# AnalogEx_1RedLedFadeInFadeOutUSB.net
KiCad netlist of a schematic drawn in EAGLE
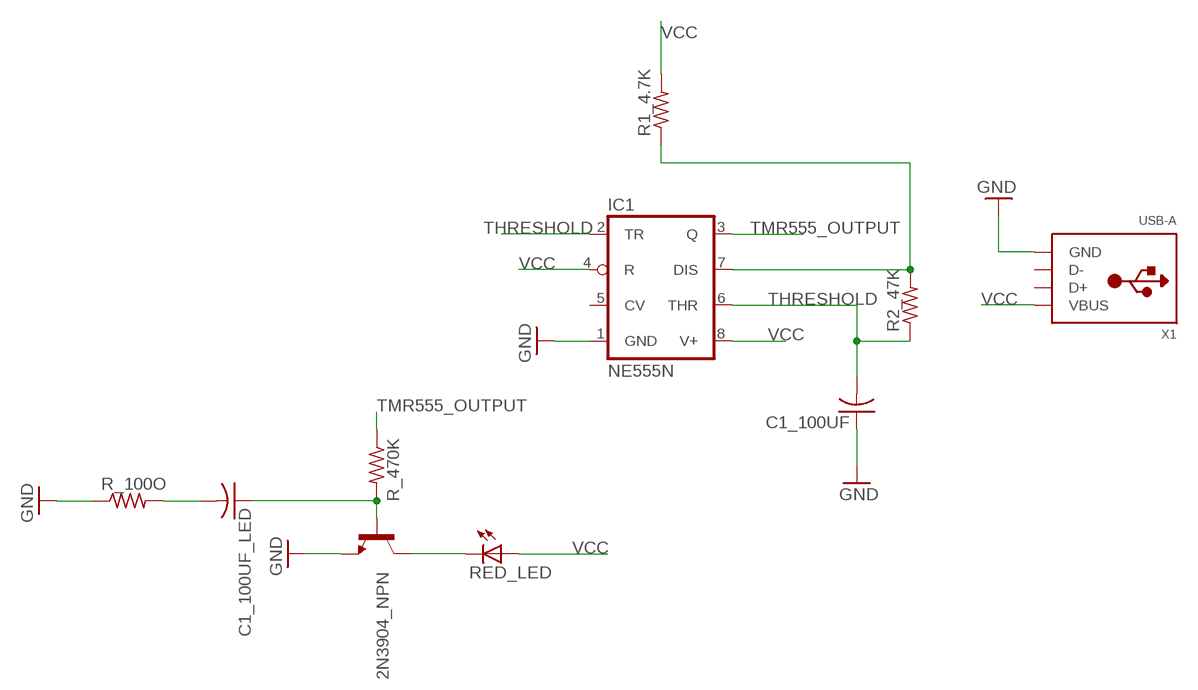
[diagram p0: schematic, sheet 1]

(export (version "E")
  (design (tool "Eeschema 10.0.6"))
  (components
    (comp (ref "2N3904_NPN")
      (value "MMBT3904LT1-NPN-SOT23-BEC")
      (footprint "eagle-import:SOT23-BEC")
      (libsource (lib "eagle-import") (part "-NPN-SOT23-BECMMBT3904LT1"))
    )
    (comp (ref "C1_100UF")
      (value "C-US025-030X050")
      (footprint "eagle-import:C025-030X050")
      (libsource (lib "eagle-import") (part "C-US025-030X050"))
    )
    (comp (ref "C1_100UF_LED")
      (value "C-US025-030X050")
      (footprint "eagle-import:C025-030X050")
      (libsource (lib "eagle-import") (part "C-US025-030X050"))
    )
    (comp (ref "IC1")
      (value "NE555N")
      (footprint "eagle-import:DIL08")
      (libsource (lib "eagle-import") (part "555NNE"))
    )
    (comp (ref "R1_4.7K")
      (value "R-US_R1206")
      (footprint "eagle-import:R1206")
      (libsource (lib "eagle-import") (part "R-US_R1206"))
    )
    (comp (ref "R2_47K")
      (value "R-US_R1206")
      (footprint "eagle-import:R1206")
      (libsource (lib "eagle-import") (part "R-US_R1206"))
    )
    (comp (ref "RED_LED")
      (value "LED5MM")
      (footprint "eagle-import:LED5MM")
      (libsource (lib "eagle-import") (part "LED5MM"))
    )
    (comp (ref "R_100O")
      (value "R-US_R1206")
      (footprint "eagle-import:R1206")
      (libsource (lib "eagle-import") (part "R-US_R1206"))
    )
    (comp (ref "R_470K")
      (value "R-US_R1206")
      (footprint "eagle-import:R1206")
      (libsource (lib "eagle-import") (part "R-US_R1206"))
    )
    (comp (ref "X1")
      (value "USB-A")
      (footprint "eagle-import:MOLEX_480371000")
      (libsource (lib "eagle-import") (part "USB-A"))
    )
  )
  (nets
    (net (code "1") (name "/THRESHOLD") (class "Default")
      (node (ref "C1_100UF") (pin "2") (pinfunction "2_2") (pintype "passive"))
      (node (ref "IC1") (pin "2") (pinfunction "TR_2") (pintype "input"))
      (node (ref "IC1") (pin "6") (pinfunction "THR_6") (pintype "input"))
      (node (ref "R2_47K") (pin "1") (pinfunction "1_1") (pintype "passive"))
    )
    (net (code "2") (name "/TMR555_OUTPUT") (class "Default")
      (node (ref "IC1") (pin "3") (pinfunction "Q_3") (pintype "output"))
      (node (ref "R_470K") (pin "1") (pinfunction "1_1") (pintype "passive"))
    )
    (net (code "3") (name "/VCC") (class "Default")
      (node (ref "IC1") (pin "4") (pinfunction "R_4") (pintype "input"))
      (node (ref "IC1") (pin "8") (pinfunction "V+_8") (pintype "power_in"))
      (node (ref "R1_4.7K") (pin "2") (pinfunction "2_2") (pintype "passive"))
      (node (ref "RED_LED") (pin "A") (pinfunction "A_A") (pintype "passive"))
      (node (ref "X1") (pin "1") (pinfunction "VBUS_1") (pintype "power_in"))
    )
    (net (code "4") (name "GND") (class "Default")
      (node (ref "2N3904_NPN") (pin "E") (pinfunction "E_E") (pintype "passive"))
      (node (ref "C1_100UF") (pin "1") (pinfunction "1_1") (pintype "passive"))
      (node (ref "IC1") (pin "1") (pinfunction "GND_1") (pintype "power_in"))
      (node (ref "R_100O") (pin "1") (pinfunction "1_1") (pintype "passive"))
      (node (ref "X1") (pin "4") (pinfunction "GND_4") (pintype "power_in"))
    )
    (net (code "5") (name "Net-(2N3904_NPN-PadB)") (class "Default")
      (node (ref "2N3904_NPN") (pin "B") (pinfunction "B_B") (pintype "passive"))
      (node (ref "C1_100UF_LED") (pin "1") (pinfunction "1_1") (pintype "passive"))
      (node (ref "R_470K") (pin "2") (pinfunction "2_2") (pintype "passive"))
    )
    (net (code "6") (name "Net-(C1_100UF_LED-Pad2)") (class "Default")
      (node (ref "C1_100UF_LED") (pin "2") (pinfunction "2_2") (pintype "passive"))
      (node (ref "R_100O") (pin "2") (pinfunction "2_2") (pintype "passive"))
    )
    (net (code "7") (name "Net-(IC1-DIS)") (class "Default")
      (node (ref "IC1") (pin "7") (pinfunction "DIS_7") (pintype "input"))
      (node (ref "R1_4.7K") (pin "1") (pinfunction "1_1") (pintype "passive"))
      (node (ref "R2_47K") (pin "2") (pinfunction "2_2") (pintype "passive"))
    )
    (net (code "8") (name "Net-(RED_LED-C)") (class "Default")
      (node (ref "2N3904_NPN") (pin "C") (pinfunction "C_C") (pintype "passive"))
      (node (ref "RED_LED") (pin "K") (pinfunction "C_K") (pintype "passive"))
    )
    (net (code "9") (name "unconnected-(IC1-CV-Pad5)") (class "Default")
      (node (ref "IC1") (pin "5") (pinfunction "CV_5") (pintype "input"))
    )
    (net (code "10") (name "unconnected-(X1-D+-Pad3)") (class "Default")
      (node (ref "X1") (pin "3") (pinfunction "D+_3") (pintype "bidirectional"))
    )
    (net (code "11") (name "unconnected-(X1-D--Pad2)") (class "Default")
      (node (ref "X1") (pin "2") (pinfunction "D-_2") (pintype "bidirectional"))
    )
  )
)
